# BHOnOfreSquareBoardCurrentSensor.net
KiCad netlist of a schematic drawn in EAGLE
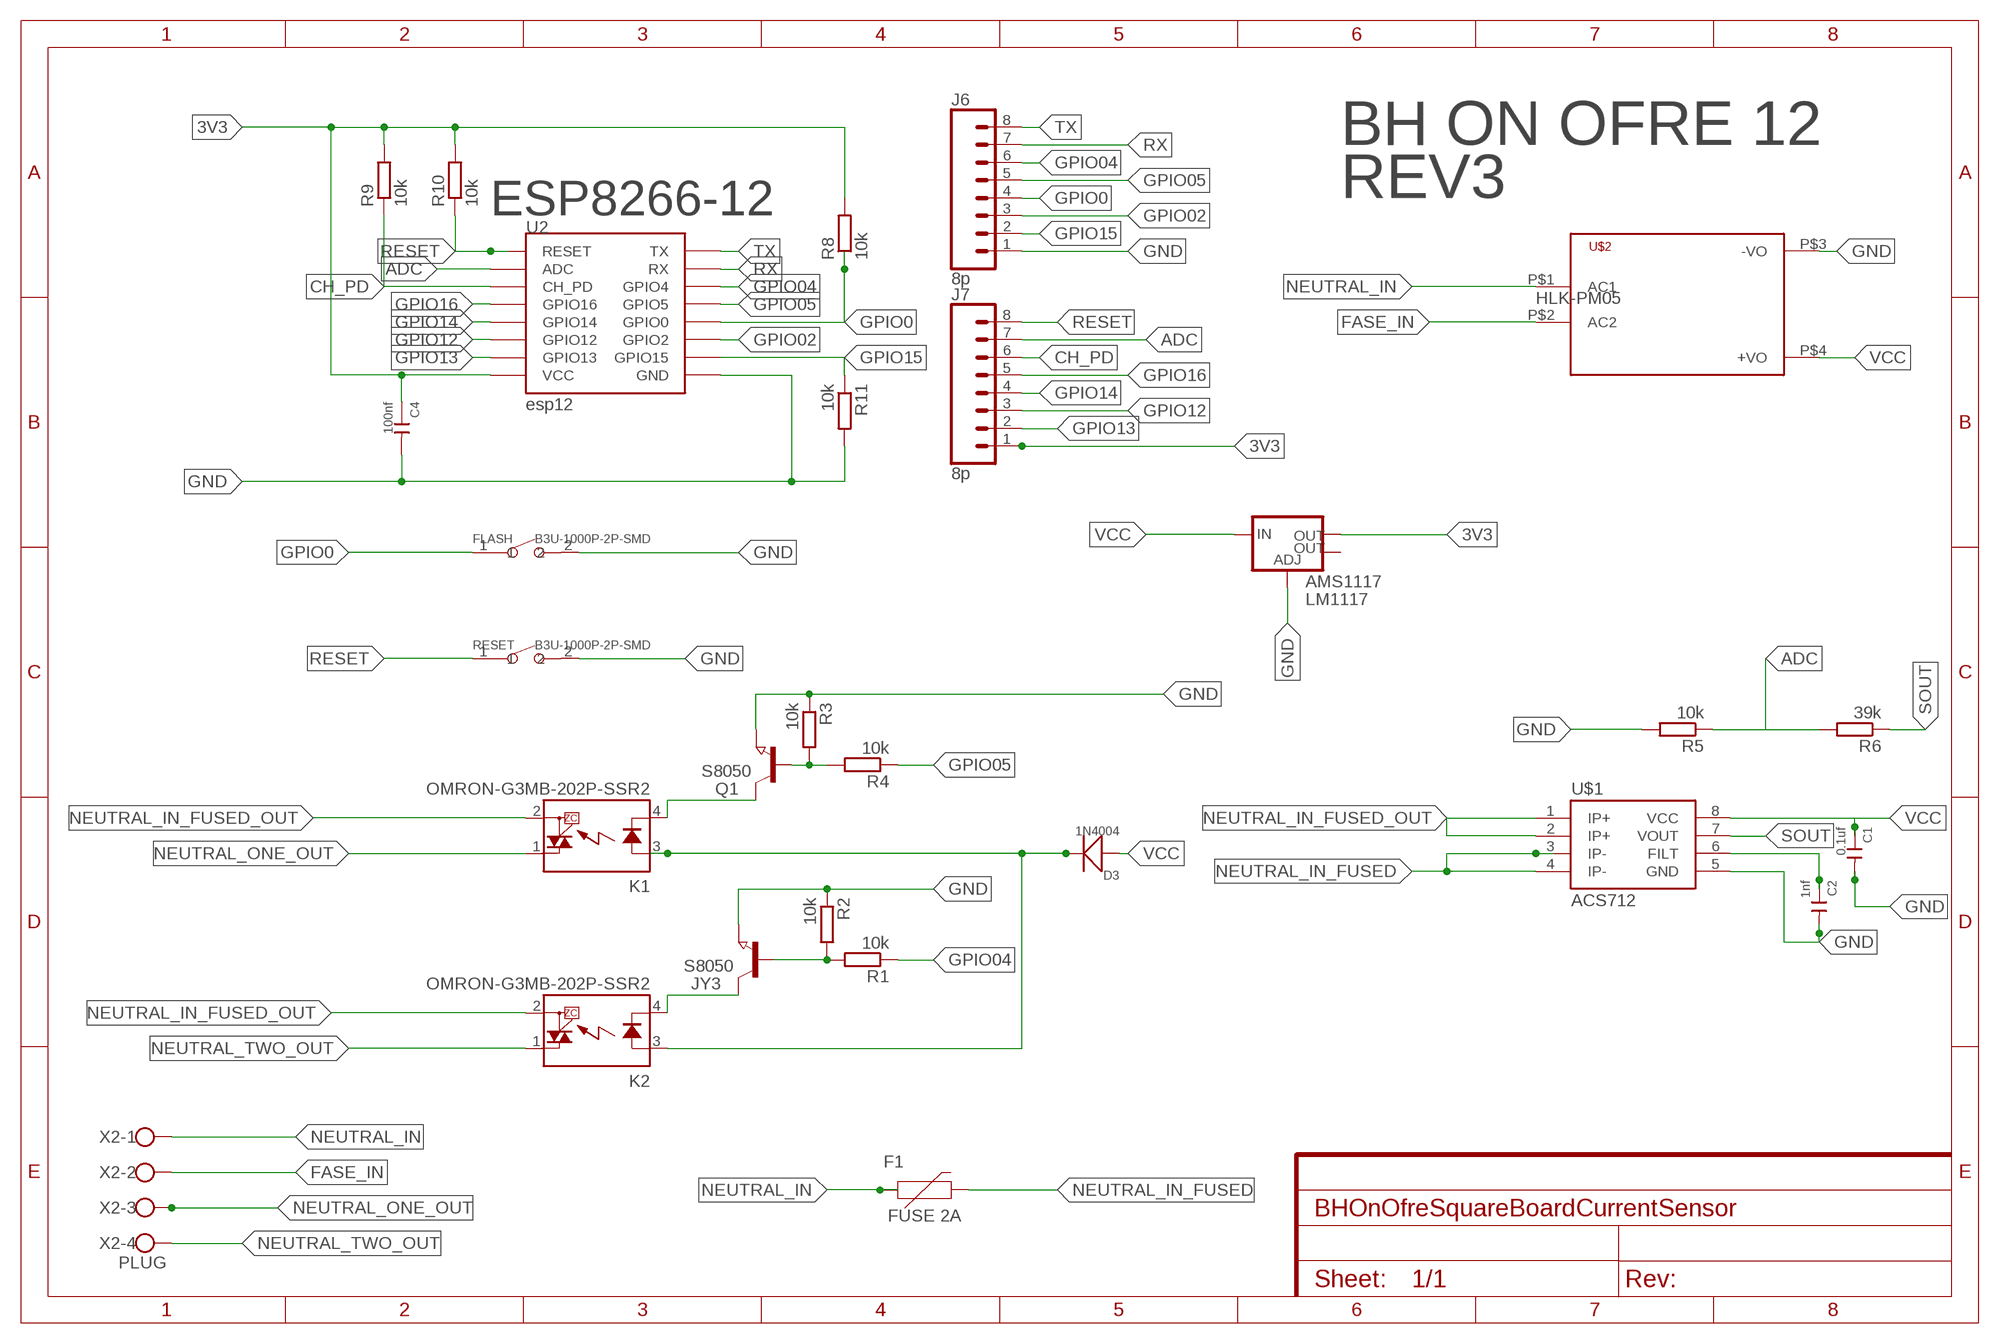
[diagram p0: schematic, sheet 1]

(export (version "E")
  (design (tool "Eeschema 10.0.6"))
  (components
    (comp (ref "AMS1117")
      (value "LM1117")
      (footprint "eagle-import:SOT223")
      (libsource (lib "eagle-import") (part "V_REG_LM1117SOT223"))
    )
    (comp (ref "C1")
      (value "0.1uf")
      (footprint "eagle-import:C0805")
      (fields (field (name "MPN") "CC0805KRX7R9BB104"))
      (libsource (lib "eagle-import") (part "CERAMIC-100NF-50V-10%-X7R(0805)"))
    )
    (comp (ref "C2")
      (value "1nf")
      (footprint "eagle-import:C0805")
      (fields (field (name "MPN") "CC0805KRX7R9BB104"))
      (libsource (lib "eagle-import") (part "CERAMIC-100NF-50V-10%-X7R(0805)"))
    )
    (comp (ref "C4")
      (value "100nf")
      (footprint "eagle-import:C0805")
      (fields (field (name "MPN") "CC0805KRX7R9BB104"))
      (libsource (lib "eagle-import") (part "CERAMIC-100NF-50V-10%-X7R(0805)"))
    )
    (comp (ref "D3")
      (value "1N4004")
      (footprint "eagle-import:DO-214AC")
      (fields (field (name "MPN") "1N4007"))
      (libsource (lib "eagle-import") (part "DIODE-GEN-PURPOSE-1KV-1A(DO-214AC)"))
    )
    (comp (ref "F1")
      (value "FUSE 2A")
      (footprint "eagle-import:PTH")
      (libsource (lib "eagle-import") (part "PPTC_PTH"))
    )
    (comp (ref "FLASH")
      (value "B3U-1000P-2P-SMD")
      (footprint "eagle-import:SW2-2.6-3.0X2.5X1.2+0.4MM")
      (libsource (lib "eagle-import") (part "SMD-BUTTON(2P-3.0X2.5X1.2+0.4MM)-B3U-1000P-2P-SMD"))
    )
    (comp (ref "J6")
      (value "8p")
      (footprint "eagle-import:1X08")
      (libsource (lib "eagle-import") (part "CONN_08{dblquote}"))
    )
    (comp (ref "J7")
      (value "8p")
      (footprint "eagle-import:1X08")
      (libsource (lib "eagle-import") (part "CONN_08{dblquote}"))
    )
    (comp (ref "JY3")
      (value "S8050")
      (footprint "eagle-import:SOT23")
      (libsource (lib "eagle-import") (part "NPN-TRANSISTOR_SOT23"))
    )
    (comp (ref "K1")
      (value "OMRON-G3MB-202P-SSR2")
      (footprint "eagle-import:OMRON-G3MB-202P-SSR")
      (fields (field (name "MPN") "S202S02F"))
      (libsource (lib "eagle-import") (part "OMRON-G3MB-202P-SSR2"))
    )
    (comp (ref "K2")
      (value "OMRON-G3MB-202P-SSR2")
      (footprint "eagle-import:OMRON-G3MB-202P-SSR")
      (fields (field (name "MPN") "S202S02F"))
      (libsource (lib "eagle-import") (part "OMRON-G3MB-202P-SSR2"))
    )
    (comp (ref "Q1")
      (value "S8050")
      (footprint "eagle-import:SOT23")
      (libsource (lib "eagle-import") (part "NPN-TRANSISTOR_SOT23"))
    )
    (comp (ref "R1")
      (value "10k")
      (footprint "eagle-import:R0603")
      (libsource (lib "eagle-import") (part "R-EU_R0603"))
    )
    (comp (ref "R2")
      (value "10k")
      (footprint "eagle-import:R0603")
      (libsource (lib "eagle-import") (part "R-EU_R0603"))
    )
    (comp (ref "R3")
      (value "10k")
      (footprint "eagle-import:R0603")
      (libsource (lib "eagle-import") (part "R-EU_R0603"))
    )
    (comp (ref "R4")
      (value "10k")
      (footprint "eagle-import:R0603")
      (libsource (lib "eagle-import") (part "R-EU_R0603"))
    )
    (comp (ref "R5")
      (value "10k")
      (footprint "eagle-import:R0603")
      (libsource (lib "eagle-import") (part "R-EU_R0603"))
    )
    (comp (ref "R6")
      (value "39k")
      (footprint "eagle-import:R0603")
      (libsource (lib "eagle-import") (part "R-EU_R0603"))
    )
    (comp (ref "R8")
      (value "10k")
      (footprint "eagle-import:R0603")
      (libsource (lib "eagle-import") (part "R-EU_R0603"))
    )
    (comp (ref "R9")
      (value "10k")
      (footprint "eagle-import:R0603")
      (libsource (lib "eagle-import") (part "R-EU_R0603"))
    )
    (comp (ref "R10")
      (value "10k")
      (footprint "eagle-import:R0603")
      (libsource (lib "eagle-import") (part "R-EU_R0603"))
    )
    (comp (ref "R11")
      (value "10k")
      (footprint "eagle-import:R0603")
      (libsource (lib "eagle-import") (part "R-EU_R0603"))
    )
    (comp (ref "RESET")
      (value "B3U-1000P-2P-SMD")
      (footprint "eagle-import:SW2-2.6-3.0X2.5X1.2+0.4MM")
      (libsource (lib "eagle-import") (part "SMD-BUTTON(2P-3.0X2.5X1.2+0.4MM)-B3U-1000P-2P-SMD"))
    )
    (comp (ref "U$1")
      (value "ACS712")
      (footprint "eagle-import:SO08")
      (libsource (lib "eagle-import") (part "ACS712"))
    )
    (comp (ref "U$2")
      (value "HKLPM01")
      (footprint "eagle-import:HKLPM01")
      (libsource (lib "eagle-import") (part "HKLPM01"))
    )
    (comp (ref "U2")
      (value "esp12")
      (footprint "eagle-import:ESP12-SMD")
      (libsource (lib "eagle-import") (part "ESP12SMD"))
    )
    (comp (ref "X2")
      (value "PLUG")
      (footprint "eagle-import:W237-4")
      (libsource (lib "eagle-import") (part "W237-4"))
    )
  )
  (nets
    (net (code "1") (name "3V3") (class "Default")
      (node (ref "AMS1117") (pin "2") (pinfunction "OUT_2") (pintype "output"))
      (node (ref "C4") (pin "1") (pinfunction "1_1") (pintype "passive"))
      (node (ref "J7") (pin "1") (pinfunction "1_1") (pintype "passive"))
      (node (ref "R10") (pin "2") (pinfunction "2_2") (pintype "passive"))
      (node (ref "R8") (pin "2") (pinfunction "2_2") (pintype "passive"))
      (node (ref "R9") (pin "2") (pinfunction "2_2") (pintype "passive"))
      (node (ref "U2") (pin "VCC") (pinfunction "VCC_VCC") (pintype "bidirectional"))
    )
    (net (code "2") (name "ADC") (class "Default")
      (node (ref "J7") (pin "7") (pinfunction "7_7") (pintype "passive"))
      (node (ref "R5") (pin "1") (pinfunction "1_1") (pintype "passive"))
      (node (ref "R6") (pin "2") (pinfunction "2_2") (pintype "passive"))
      (node (ref "U2") (pin "ADC") (pinfunction "ADC_ADC") (pintype "bidirectional"))
    )
    (net (code "3") (name "CH_PD") (class "Default")
      (node (ref "J7") (pin "6") (pinfunction "6_6") (pintype "passive"))
      (node (ref "R9") (pin "1") (pinfunction "1_1") (pintype "passive"))
      (node (ref "U2") (pin "CH_PD") (pinfunction "CH_PD_CH_PD") (pintype "bidirectional"))
    )
    (net (code "4") (name "FASE_IN") (class "Default")
      (node (ref "U$2") (pin "P$2") (pinfunction "AC2_P$2") (pintype "bidirectional"))
      (node (ref "X2") (pin "2") (pinfunction "KL_2") (pintype "passive"))
    )
    (net (code "5") (name "GND") (class "Default")
      (node (ref "AMS1117") (pin "1") (pinfunction "ADJ_1") (pintype "input"))
      (node (ref "C1") (pin "2") (pinfunction "2_2") (pintype "passive"))
      (node (ref "C2") (pin "2") (pinfunction "2_2") (pintype "passive"))
      (node (ref "C4") (pin "2") (pinfunction "2_2") (pintype "passive"))
      (node (ref "FLASH") (pin "2") (pinfunction "2_2") (pintype "bidirectional"))
      (node (ref "J6") (pin "1") (pinfunction "1_1") (pintype "passive"))
      (node (ref "JY3") (pin "2") (pinfunction "E_2") (pintype "passive"))
      (node (ref "Q1") (pin "2") (pinfunction "E_2") (pintype "passive"))
      (node (ref "R11") (pin "2") (pinfunction "2_2") (pintype "passive"))
      (node (ref "R2") (pin "1") (pinfunction "1_1") (pintype "passive"))
      (node (ref "R3") (pin "1") (pinfunction "1_1") (pintype "passive"))
      (node (ref "R5") (pin "2") (pinfunction "2_2") (pintype "passive"))
      (node (ref "RESET") (pin "2") (pinfunction "2_2") (pintype "bidirectional"))
      (node (ref "U$1") (pin "5") (pinfunction "GND_5") (pintype "bidirectional"))
      (node (ref "U$2") (pin "P$3") (pinfunction "-VO_P$3") (pintype "bidirectional"))
      (node (ref "U2") (pin "GND") (pinfunction "GND_GND") (pintype "bidirectional"))
    )
    (net (code "6") (name "GPIO0") (class "Default")
      (node (ref "FLASH") (pin "1") (pinfunction "1_1") (pintype "bidirectional"))
      (node (ref "J6") (pin "4") (pinfunction "4_4") (pintype "passive"))
      (node (ref "R8") (pin "1") (pinfunction "1_1") (pintype "passive"))
      (node (ref "U2") (pin "GPIO0") (pinfunction "GPIO0_GPIO0") (pintype "bidirectional"))
    )
    (net (code "7") (name "GPIO02") (class "Default")
      (node (ref "J6") (pin "3") (pinfunction "3_3") (pintype "passive"))
      (node (ref "U2") (pin "GPIO2") (pinfunction "GPIO2_GPIO2") (pintype "bidirectional"))
    )
    (net (code "8") (name "GPIO04") (class "Default")
      (node (ref "J6") (pin "6") (pinfunction "6_6") (pintype "passive"))
      (node (ref "R1") (pin "1") (pinfunction "1_1") (pintype "passive"))
      (node (ref "U2") (pin "GPIO4") (pinfunction "GPIO4_GPIO4") (pintype "bidirectional"))
    )
    (net (code "9") (name "GPIO05") (class "Default")
      (node (ref "J6") (pin "5") (pinfunction "5_5") (pintype "passive"))
      (node (ref "R4") (pin "1") (pinfunction "1_1") (pintype "passive"))
      (node (ref "U2") (pin "GPIO5") (pinfunction "GPIO5_GPIO5") (pintype "bidirectional"))
    )
    (net (code "10") (name "GPIO12") (class "Default")
      (node (ref "J7") (pin "3") (pinfunction "3_3") (pintype "passive"))
      (node (ref "U2") (pin "GPIO12") (pinfunction "GPIO12_GPIO12") (pintype "bidirectional"))
    )
    (net (code "11") (name "GPIO13") (class "Default")
      (node (ref "J7") (pin "2") (pinfunction "2_2") (pintype "passive"))
      (node (ref "U2") (pin "GPIO13") (pinfunction "GPIO13_GPIO13") (pintype "bidirectional"))
    )
    (net (code "12") (name "GPIO14") (class "Default")
      (node (ref "J7") (pin "4") (pinfunction "4_4") (pintype "passive"))
      (node (ref "U2") (pin "GPIO14") (pinfunction "GPIO14_GPIO14") (pintype "bidirectional"))
    )
    (net (code "13") (name "GPIO15") (class "Default")
      (node (ref "J6") (pin "2") (pinfunction "2_2") (pintype "passive"))
      (node (ref "R11") (pin "1") (pinfunction "1_1") (pintype "passive"))
      (node (ref "U2") (pin "GPIO15") (pinfunction "GPIO15_GPIO15") (pintype "bidirectional"))
    )
    (net (code "14") (name "GPIO16") (class "Default")
      (node (ref "J7") (pin "5") (pinfunction "5_5") (pintype "passive"))
      (node (ref "U2") (pin "GPIO16") (pinfunction "GPIO16_GPIO16") (pintype "bidirectional"))
    )
    (net (code "15") (name "NEUTRAL_IN") (class "Default")
      (node (ref "F1") (pin "P$1") (pinfunction "1_P$1") (pintype "bidirectional"))
      (node (ref "U$2") (pin "P$1") (pinfunction "AC1_P$1") (pintype "bidirectional"))
      (node (ref "X2") (pin "1") (pinfunction "KL_1") (pintype "passive"))
    )
    (net (code "16") (name "NEUTRAL_IN_FUSED") (class "Default")
      (node (ref "F1") (pin "P$2") (pinfunction "2_P$2") (pintype "bidirectional"))
      (node (ref "U$1") (pin "3") (pinfunction "IP-_3") (pintype "bidirectional"))
      (node (ref "U$1") (pin "4") (pinfunction "IP-_4") (pintype "bidirectional"))
    )
    (net (code "17") (name "NEUTRAL_IN_FUSED_OUT") (class "Default")
      (node (ref "K1") (pin "2") (pinfunction "DS2_2") (pintype "passive"))
      (node (ref "K2") (pin "2") (pinfunction "DS2_2") (pintype "passive"))
      (node (ref "U$1") (pin "1") (pinfunction "IP+_1") (pintype "bidirectional"))
      (node (ref "U$1") (pin "2") (pinfunction "IP+_2") (pintype "bidirectional"))
    )
    (net (code "18") (name "NEUTRAL_ONE_OUT") (class "Default")
      (node (ref "K1") (pin "1") (pinfunction "DS1_1") (pintype "passive"))
      (node (ref "X2") (pin "3") (pinfunction "KL_3") (pintype "passive"))
    )
    (net (code "19") (name "NEUTRAL_TWO_OUT") (class "Default")
      (node (ref "K2") (pin "1") (pinfunction "DS1_1") (pintype "passive"))
      (node (ref "X2") (pin "4") (pinfunction "KL_4") (pintype "passive"))
    )
    (net (code "20") (name "Net-(D3--)") (class "Default")
      (node (ref "D3") (pin "2") (pinfunction "-_2") (pintype "passive"))
      (node (ref "K1") (pin "3") (pinfunction "A_3") (pintype "passive"))
      (node (ref "K2") (pin "3") (pinfunction "A_3") (pintype "passive"))
    )
    (net (code "21") (name "Net-(JY3-B)") (class "Default")
      (node (ref "JY3") (pin "1") (pinfunction "B_1") (pintype "passive"))
      (node (ref "R1") (pin "2") (pinfunction "2_2") (pintype "passive"))
      (node (ref "R2") (pin "2") (pinfunction "2_2") (pintype "passive"))
    )
    (net (code "22") (name "Net-(JY3-C)") (class "Default")
      (node (ref "JY3") (pin "3") (pinfunction "C_3") (pintype "passive"))
      (node (ref "K2") (pin "4") (pinfunction "K_4") (pintype "passive"))
    )
    (net (code "23") (name "Net-(K1-K)") (class "Default")
      (node (ref "K1") (pin "4") (pinfunction "K_4") (pintype "passive"))
      (node (ref "Q1") (pin "3") (pinfunction "C_3") (pintype "passive"))
    )
    (net (code "24") (name "Net-(Q1-B)") (class "Default")
      (node (ref "Q1") (pin "1") (pinfunction "B_1") (pintype "passive"))
      (node (ref "R3") (pin "2") (pinfunction "2_2") (pintype "passive"))
      (node (ref "R4") (pin "2") (pinfunction "2_2") (pintype "passive"))
    )
    (net (code "25") (name "Net-(U$1-FILT)") (class "Default")
      (node (ref "C2") (pin "1") (pinfunction "1_1") (pintype "passive"))
      (node (ref "U$1") (pin "6") (pinfunction "FILT_6") (pintype "bidirectional"))
    )
    (net (code "26") (name "RESET") (class "Default")
      (node (ref "J7") (pin "8") (pinfunction "8_8") (pintype "passive"))
      (node (ref "R10") (pin "1") (pinfunction "1_1") (pintype "passive"))
      (node (ref "RESET") (pin "1") (pinfunction "1_1") (pintype "bidirectional"))
      (node (ref "U2") (pin "RESET") (pinfunction "RESET_RESET") (pintype "bidirectional"))
    )
    (net (code "27") (name "RX") (class "Default")
      (node (ref "J6") (pin "7") (pinfunction "7_7") (pintype "passive"))
      (node (ref "U2") (pin "RXD0") (pinfunction "RX_RXD0") (pintype "bidirectional"))
    )
    (net (code "28") (name "SOUT") (class "Default")
      (node (ref "R6") (pin "1") (pinfunction "1_1") (pintype "passive"))
      (node (ref "U$1") (pin "7") (pinfunction "VOUT_7") (pintype "bidirectional"))
    )
    (net (code "29") (name "TX") (class "Default")
      (node (ref "J6") (pin "8") (pinfunction "8_8") (pintype "passive"))
      (node (ref "U2") (pin "TXD0") (pinfunction "TX_TXD0") (pintype "bidirectional"))
    )
    (net (code "30") (name "VCC") (class "Default")
      (node (ref "AMS1117") (pin "3") (pinfunction "IN_3") (pintype "input"))
      (node (ref "C1") (pin "1") (pinfunction "1_1") (pintype "passive"))
      (node (ref "D3") (pin "1") (pinfunction "+_1") (pintype "passive"))
      (node (ref "U$1") (pin "8") (pinfunction "VCC_8") (pintype "bidirectional"))
      (node (ref "U$2") (pin "P$4") (pinfunction "+VO_P$4") (pintype "bidirectional"))
    )
    (net (code "31") (name "unconnected-(AMS1117-OUT-Pad4)") (class "Default")
      (node (ref "AMS1117") (pin "4") (pinfunction "OUT_4") (pintype "output"))
    )
  )
)
